# Sheet5_old.net
KiCad netlist of a schematic drawn in Altium Designer
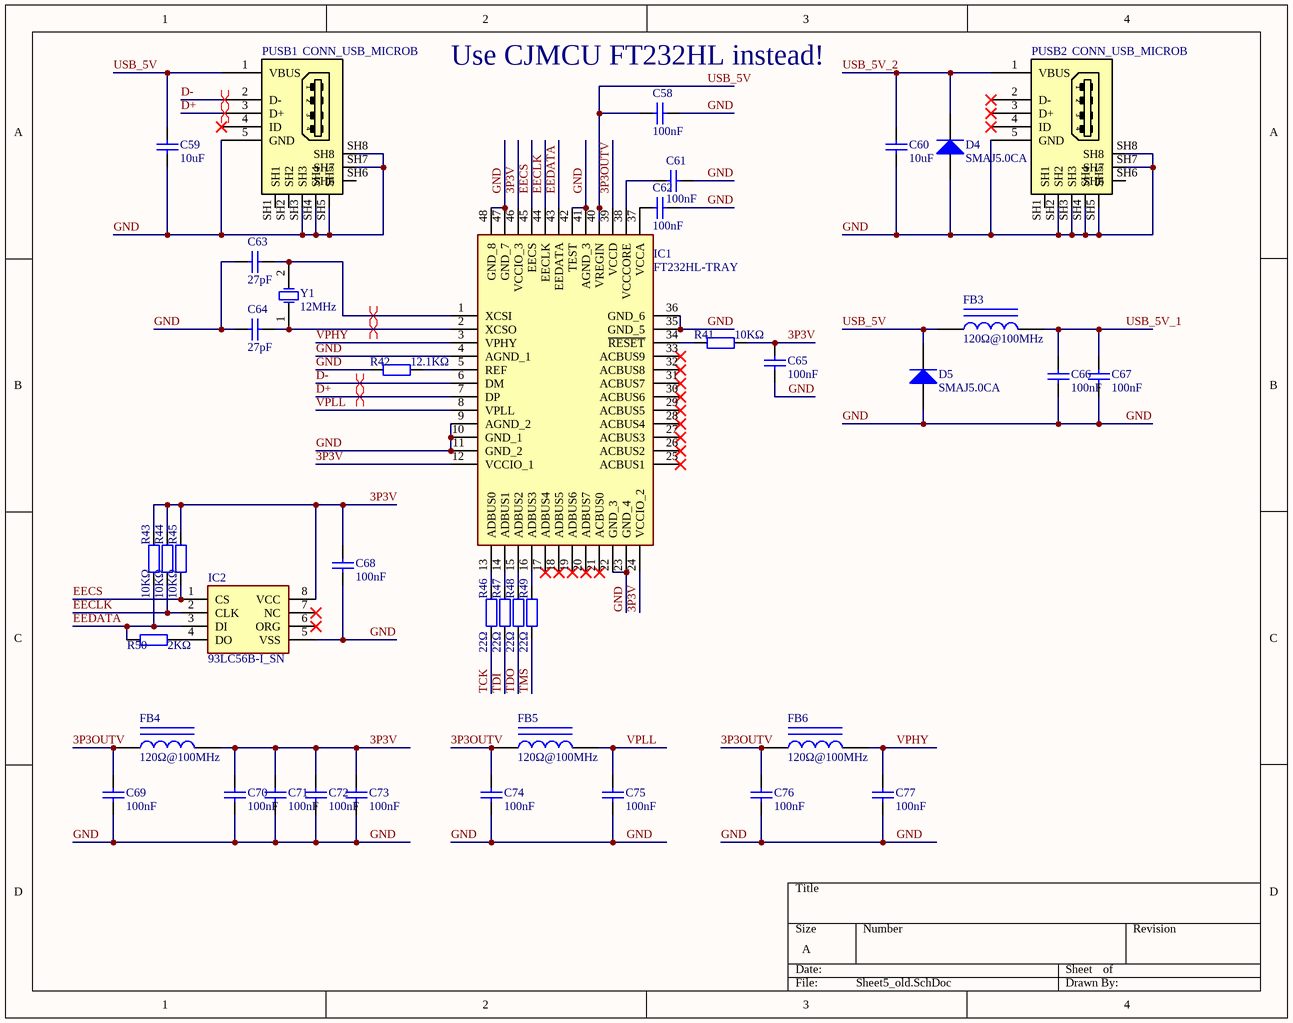
[diagram p0: Sheet5_old.SchDoc]

(export (version "E")
  (design (tool "Eeschema 10.0.6"))
  (components
    (comp (ref "C58")
      (value "100nF")
      (footprint "1206_C")
      (description "贴片电容")
      (libsource (lib "Cap") (part "1206 100nF (104) 10% 50V"))
    )
    (comp (ref "C59")
      (value "10uF")
      (footprint "1206_C")
      (description "贴片电容")
      (libsource (lib "Cap") (part "1206 10uF (106) 10% 50V"))
    )
    (comp (ref "C60")
      (value "10uF")
      (footprint "1206_C")
      (description "贴片电容")
      (libsource (lib "Cap") (part "1206 10uF (106) 10% 50V"))
    )
    (comp (ref "C61")
      (value "100nF")
      (footprint "1206_C")
      (description "贴片电容")
      (libsource (lib "Cap") (part "1206 100nF (104) 10% 50V"))
    )
    (comp (ref "C62")
      (value "100nF")
      (footprint "1206_C")
      (description "贴片电容")
      (libsource (lib "Cap") (part "1206 100nF (104) 10% 50V"))
    )
    (comp (ref "C63")
      (value "27pF")
      (footprint "0805_C")
      (description "贴片电容")
      (libsource (lib "Cap") (part "0805 27pF (270) 5% 50V"))
    )
    (comp (ref "C64")
      (value "27pF")
      (footprint "0805_C")
      (description "贴片电容")
      (libsource (lib "Cap") (part "0805 27pF (270) 5% 50V"))
    )
    (comp (ref "C65")
      (value "100nF")
      (footprint "1206_C")
      (description "贴片电容")
      (libsource (lib "Cap") (part "1206 100nF (104) 10% 50V"))
    )
    (comp (ref "C66")
      (value "100nF")
      (footprint "1206_C")
      (description "贴片电容")
      (libsource (lib "Cap") (part "1206 100nF (104) 10% 50V"))
    )
    (comp (ref "C67")
      (value "100nF")
      (footprint "1206_C")
      (description "贴片电容")
      (libsource (lib "Cap") (part "1206 100nF (104) 10% 50V"))
    )
    (comp (ref "C68")
      (value "100nF")
      (footprint "1206_C")
      (description "贴片电容")
      (libsource (lib "Cap") (part "1206 100nF (104) 10% 50V"))
    )
    (comp (ref "C69")
      (value "100nF")
      (footprint "1206_C")
      (description "贴片电容")
      (libsource (lib "Cap") (part "1206 100nF (104) 10% 50V"))
    )
    (comp (ref "C70")
      (value "100nF")
      (footprint "1206_C")
      (description "贴片电容")
      (libsource (lib "Cap") (part "1206 100nF (104) 10% 50V"))
    )
    (comp (ref "C71")
      (value "100nF")
      (footprint "1206_C")
      (description "贴片电容")
      (libsource (lib "Cap") (part "1206 100nF (104) 10% 50V"))
    )
    (comp (ref "C72")
      (value "100nF")
      (footprint "1206_C")
      (description "贴片电容")
      (libsource (lib "Cap") (part "1206 100nF (104) 10% 50V"))
    )
    (comp (ref "C73")
      (value "100nF")
      (footprint "1206_C")
      (description "贴片电容")
      (libsource (lib "Cap") (part "1206 100nF (104) 10% 50V"))
    )
    (comp (ref "C74")
      (value "100nF")
      (footprint "1206_C")
      (description "贴片电容")
      (libsource (lib "Cap") (part "1206 100nF (104) 10% 50V"))
    )
    (comp (ref "C75")
      (value "100nF")
      (footprint "1206_C")
      (description "贴片电容")
      (libsource (lib "Cap") (part "1206 100nF (104) 10% 50V"))
    )
    (comp (ref "C76")
      (value "100nF")
      (footprint "1206_C")
      (description "贴片电容")
      (libsource (lib "Cap") (part "1206 100nF (104) 10% 50V"))
    )
    (comp (ref "C77")
      (value "100nF")
      (footprint "1206_C")
      (description "贴片电容")
      (libsource (lib "Cap") (part "1206 100nF (104) 10% 50V"))
    )
    (comp (ref "D4")
      (value "SMAJ5.0CA")
      (footprint "SMA(DO-214AC)_S1")
      (description "二极管 TVS")
      (libsource (lib "Diode") (part "SMA(DO-214AC) SS210"))
    )
    (comp (ref "D5")
      (value "SMAJ5.0CA")
      (footprint "SMA(DO-214AC)_S1")
      (description "二极管 TVS")
      (libsource (lib "Diode") (part "SMA(DO-214AC) SS210"))
    )
    (comp (ref "FB3")
      (value "120Ω@100MHz")
      (footprint "0805_L")
      (description "贴片磁珠")
      (libsource (lib "IUD") (part "0805 100Ω 25% 100MHz"))
    )
    (comp (ref "FB4")
      (value "120Ω@100MHz")
      (footprint "0805_L")
      (description "贴片磁珠")
      (libsource (lib "IUD") (part "0805 100Ω 25% 100MHz"))
    )
    (comp (ref "FB5")
      (value "120Ω@100MHz")
      (footprint "0805_L")
      (description "贴片磁珠")
      (libsource (lib "IUD") (part "0805 100Ω 25% 100MHz"))
    )
    (comp (ref "FB6")
      (value "120Ω@100MHz")
      (footprint "0805_L")
      (description "贴片磁珠")
      (libsource (lib "IUD") (part "0805 100Ω 25% 100MHz"))
    )
    (comp (ref "IC1")
      (value "FT232HL-TRAY")
      (footprint "SamacSys:QFP50P900X900X160-48N")
      (description "Integrated Circuit")
      (fields (field (name "MOUSER PART NUMBER") "895-FT232HL-TRAY"))
      (libsource (lib "*") (part "FT232HL-TRAY"))
    )
    (comp (ref "IC2")
      (value "93LC56B-I_SN")
      (footprint "SamacSys:SOIC127P600X175-8N")
      (description "Integrated Circuit")
      (fields
        (field (name "MANUFACTURER_PART_NUMBER") "93LC56B-I/SN")
        (field (name "MOUSER PART NUMBER") "579-93LC56BISN")
      )
      (libsource (lib "*") (part "93LC56B-I_SN"))
    )
    (comp (ref "PUSB1")
      (value "CONN_USB_MICROB")
      (footprint "USB_MICRO_B_BM_SHT1")
      (description "CONN, USB, MICRO B, R/A, SMD, BOTTOM MOUNT, SHT")
      (fields (field (name "MANF_P#") "47590-0001") (field (name "MANF") "MOLEX"))
      (libsource (lib "Connector USB") (part "CONN_USB_MICRO_B_BM_SHT1"))
    )
    (comp (ref "PUSB2")
      (value "CONN_USB_MICROB")
      (footprint "USB_MICRO_B_BM_SHT1")
      (description "CONN, USB, MICRO B, R/A, SMD, BOTTOM MOUNT, SHT")
      (fields (field (name "MANF_P#") "47590-0001") (field (name "MANF") "MOLEX"))
      (libsource (lib "Connector USB") (part "CONN_USB_MICRO_B_BM_SHT1"))
    )
    (comp (ref "R41")
      (value "10KΩ")
      (footprint "1206_R")
      (description "贴片电阻")
      (libsource (lib "RES") (part "1206 10KΩ (1002) 1%"))
    )
    (comp (ref "R42")
      (value "12.1KΩ")
      (footprint "0805_R")
      (description "贴片电阻 12.1k")
      (libsource (lib "RES") (part "0805 12KΩ (1202) 1%"))
    )
    (comp (ref "R43")
      (value "10KΩ")
      (footprint "1206_R")
      (description "贴片电阻")
      (libsource (lib "") (part "1206 10KΩ (1002) 1%_1"))
    )
    (comp (ref "R44")
      (value "10KΩ")
      (footprint "1206_R")
      (description "贴片电阻")
      (libsource (lib "") (part "1206 10KΩ (1002) 1%_1"))
    )
    (comp (ref "R45")
      (value "10KΩ")
      (footprint "1206_R")
      (description "贴片电阻")
      (libsource (lib "") (part "1206 10KΩ (1002) 1%_1"))
    )
    (comp (ref "R46")
      (value "22Ω")
      (footprint "1206_R")
      (description "贴片电阻")
      (libsource (lib "RES") (part "1206 22Ω (22R0) 1%"))
    )
    (comp (ref "R47")
      (value "22Ω")
      (footprint "1206_R")
      (description "贴片电阻")
      (libsource (lib "RES") (part "1206 22Ω (22R0) 1%"))
    )
    (comp (ref "R48")
      (value "22Ω")
      (footprint "1206_R")
      (description "贴片电阻")
      (libsource (lib "RES") (part "1206 22Ω (22R0) 1%"))
    )
    (comp (ref "R49")
      (value "22Ω")
      (footprint "1206_R")
      (description "贴片电阻")
      (libsource (lib "RES") (part "1206 22Ω (22R0) 1%"))
    )
    (comp (ref "R50")
      (value "2KΩ")
      (footprint "1206_R")
      (description "贴片电阻")
      (libsource (lib "RES") (part "1206 2KΩ (2001) 1%"))
    )
    (comp (ref "Y1")
      (value "12MHz")
      (footprint "SMD-5032_2P")
      (description "贴片晶振 12MHz")
      (libsource (lib "CrystalOscillator") (part "SMD-5032_2P 11.0592MHZ 20PF 20PPM"))
    )
  )
  (nets
    (net (code "1") (name "/3P3OUTV") (class "Default")
      (node (ref "C69") (pin "2") (pinfunction "2_2") (pintype "passive"))
      (node (ref "C74") (pin "2") (pinfunction "2_2") (pintype "passive"))
      (node (ref "C76") (pin "2") (pinfunction "2_2") (pintype "passive"))
      (node (ref "FB4") (pin "1") (pinfunction "1_1") (pintype "passive"))
      (node (ref "FB5") (pin "1") (pinfunction "1_1") (pintype "passive"))
      (node (ref "FB6") (pin "1") (pinfunction "1_1") (pintype "passive"))
      (node (ref "IC1") (pin "39") (pinfunction "VCCD_39") (pintype "passive"))
    )
    (net (code "2") (name "/3P3V") (class "Default")
      (node (ref "C65") (pin "2") (pinfunction "2_2") (pintype "passive"))
      (node (ref "C68") (pin "2") (pinfunction "2_2") (pintype "passive"))
      (node (ref "C70") (pin "2") (pinfunction "2_2") (pintype "passive"))
      (node (ref "C71") (pin "2") (pinfunction "2_2") (pintype "passive"))
      (node (ref "C72") (pin "2") (pinfunction "2_2") (pintype "passive"))
      (node (ref "C73") (pin "2") (pinfunction "2_2") (pintype "passive"))
      (node (ref "FB4") (pin "2") (pinfunction "2_2") (pintype "passive"))
      (node (ref "IC1") (pin "12") (pinfunction "VCCIO_1_12") (pintype "passive"))
      (node (ref "IC1") (pin "24") (pinfunction "VCCIO_2_24") (pintype "passive"))
      (node (ref "IC1") (pin "46") (pinfunction "VCCIO_3_46") (pintype "passive"))
      (node (ref "IC2") (pin "8") (pinfunction "VCC_8") (pintype "passive"))
      (node (ref "R41") (pin "2") (pinfunction "2_2") (pintype "passive"))
      (node (ref "R43") (pin "2") (pinfunction "2_2") (pintype "passive"))
      (node (ref "R44") (pin "2") (pinfunction "2_2") (pintype "passive"))
      (node (ref "R45") (pin "2") (pinfunction "2_2") (pintype "passive"))
    )
    (net (code "3") (name "/D+") (class "Default")
      (node (ref "IC1") (pin "7") (pinfunction "DP_7") (pintype "passive"))
      (node (ref "PUSB1") (pin "3") (pinfunction "D+_3") (pintype "passive"))
    )
    (net (code "4") (name "/D-") (class "Default")
      (node (ref "IC1") (pin "6") (pinfunction "DM_6") (pintype "passive"))
      (node (ref "PUSB1") (pin "2") (pinfunction "D-_2") (pintype "passive"))
    )
    (net (code "5") (name "/EECLK") (class "Default")
      (node (ref "IC1") (pin "44") (pinfunction "EECLK_44") (pintype "passive"))
      (node (ref "IC2") (pin "2") (pinfunction "CLK_2") (pintype "passive"))
      (node (ref "R44") (pin "1") (pinfunction "1_1") (pintype "passive"))
    )
    (net (code "6") (name "/EECS") (class "Default")
      (node (ref "IC1") (pin "45") (pinfunction "EECS_45") (pintype "passive"))
      (node (ref "IC2") (pin "1") (pinfunction "CS_1") (pintype "passive"))
      (node (ref "R45") (pin "1") (pinfunction "1_1") (pintype "passive"))
    )
    (net (code "7") (name "/EEDATA") (class "Default")
      (node (ref "IC1") (pin "43") (pinfunction "EEDATA_43") (pintype "passive"))
      (node (ref "IC2") (pin "3") (pinfunction "DI_3") (pintype "passive"))
      (node (ref "R43") (pin "1") (pinfunction "1_1") (pintype "passive"))
      (node (ref "R50") (pin "1") (pinfunction "1_1") (pintype "passive"))
    )
    (net (code "8") (name "/GND") (class "Default")
      (node (ref "C58") (pin "2") (pinfunction "2_2") (pintype "passive"))
      (node (ref "C59") (pin "1") (pinfunction "1_1") (pintype "passive"))
      (node (ref "C60") (pin "1") (pinfunction "1_1") (pintype "passive"))
      (node (ref "C61") (pin "2") (pinfunction "2_2") (pintype "passive"))
      (node (ref "C62") (pin "2") (pinfunction "2_2") (pintype "passive"))
      (node (ref "C63") (pin "1") (pinfunction "1_1") (pintype "passive"))
      (node (ref "C64") (pin "1") (pinfunction "1_1") (pintype "passive"))
      (node (ref "C65") (pin "1") (pinfunction "1_1") (pintype "passive"))
      (node (ref "C66") (pin "1") (pinfunction "1_1") (pintype "passive"))
      (node (ref "C67") (pin "1") (pinfunction "1_1") (pintype "passive"))
      (node (ref "C68") (pin "1") (pinfunction "1_1") (pintype "passive"))
      (node (ref "C69") (pin "1") (pinfunction "1_1") (pintype "passive"))
      (node (ref "C70") (pin "1") (pinfunction "1_1") (pintype "passive"))
      (node (ref "C71") (pin "1") (pinfunction "1_1") (pintype "passive"))
      (node (ref "C72") (pin "1") (pinfunction "1_1") (pintype "passive"))
      (node (ref "C73") (pin "1") (pinfunction "1_1") (pintype "passive"))
      (node (ref "C74") (pin "1") (pinfunction "1_1") (pintype "passive"))
      (node (ref "C75") (pin "1") (pinfunction "1_1") (pintype "passive"))
      (node (ref "C76") (pin "1") (pinfunction "1_1") (pintype "passive"))
      (node (ref "C77") (pin "1") (pinfunction "1_1") (pintype "passive"))
      (node (ref "D4") (pin "1") (pinfunction "A_1") (pintype "passive"))
      (node (ref "D5") (pin "1") (pinfunction "A_1") (pintype "passive"))
      (node (ref "IC1") (pin "10") (pinfunction "GND_1_10") (pintype "passive"))
      (node (ref "IC1") (pin "11") (pinfunction "GND_2_11") (pintype "passive"))
      (node (ref "IC1") (pin "22") (pinfunction "GND_3_22") (pintype "passive"))
      (node (ref "IC1") (pin "23") (pinfunction "GND_4_23") (pintype "passive"))
      (node (ref "IC1") (pin "35") (pinfunction "GND_5_35") (pintype "passive"))
      (node (ref "IC1") (pin "36") (pinfunction "GND_6_36") (pintype "passive"))
      (node (ref "IC1") (pin "4") (pinfunction "AGND_1_4") (pintype "passive"))
      (node (ref "IC1") (pin "41") (pinfunction "AGND_3_41") (pintype "passive"))
      (node (ref "IC1") (pin "42") (pinfunction "TEST_42") (pintype "passive"))
      (node (ref "IC1") (pin "47") (pinfunction "GND_7_47") (pintype "passive"))
      (node (ref "IC1") (pin "48") (pinfunction "GND_8_48") (pintype "passive"))
      (node (ref "IC1") (pin "9") (pinfunction "AGND_2_9") (pintype "passive"))
      (node (ref "IC2") (pin "5") (pinfunction "VSS_5") (pintype "passive"))
      (node (ref "PUSB1") (pin "5") (pinfunction "GND_5") (pintype "power_in"))
      (node (ref "PUSB1") (pin "SH3") (pinfunction "SH3_SH3") (pintype "passive"))
      (node (ref "PUSB1") (pin "SH4") (pinfunction "SH4_SH4") (pintype "passive"))
      (node (ref "PUSB1") (pin "SH5") (pinfunction "SH5_SH5") (pintype "passive"))
      (node (ref "PUSB1") (pin "SH7") (pinfunction "SH7_SH7") (pintype "passive"))
      (node (ref "PUSB1") (pin "SH8") (pinfunction "SH8_SH8") (pintype "passive"))
      (node (ref "PUSB2") (pin "5") (pinfunction "GND_5") (pintype "power_in"))
      (node (ref "PUSB2") (pin "SH2") (pinfunction "SH2_SH2") (pintype "passive"))
      (node (ref "PUSB2") (pin "SH3") (pinfunction "SH3_SH3") (pintype "passive"))
      (node (ref "PUSB2") (pin "SH4") (pinfunction "SH4_SH4") (pintype "passive"))
      (node (ref "PUSB2") (pin "SH5") (pinfunction "SH5_SH5") (pintype "passive"))
      (node (ref "PUSB2") (pin "SH7") (pinfunction "SH7_SH7") (pintype "passive"))
      (node (ref "PUSB2") (pin "SH8") (pinfunction "SH8_SH8") (pintype "passive"))
      (node (ref "R42") (pin "1") (pinfunction "1_1") (pintype "passive"))
    )
    (net (code "9") (name "/TCK") (class "Default")
      (node (ref "R46") (pin "1") (pinfunction "1_1") (pintype "passive"))
    )
    (net (code "10") (name "/TDI") (class "Default")
      (node (ref "R47") (pin "1") (pinfunction "1_1") (pintype "passive"))
    )
    (net (code "11") (name "/TDO") (class "Default")
      (node (ref "R48") (pin "1") (pinfunction "1_1") (pintype "passive"))
    )
    (net (code "12") (name "/TMS") (class "Default")
      (node (ref "R49") (pin "1") (pinfunction "1_1") (pintype "passive"))
    )
    (net (code "13") (name "/USB_5V") (class "Default")
      (node (ref "C58") (pin "1") (pinfunction "1_1") (pintype "passive"))
      (node (ref "C59") (pin "2") (pinfunction "2_2") (pintype "passive"))
      (node (ref "D5") (pin "2") (pinfunction "K_2") (pintype "passive"))
      (node (ref "FB3") (pin "1") (pinfunction "1_1") (pintype "passive"))
      (node (ref "IC1") (pin "40") (pinfunction "VREGIN_40") (pintype "passive"))
      (node (ref "PUSB1") (pin "1") (pinfunction "VBUS_1") (pintype "power_in"))
    )
    (net (code "14") (name "/USB_5V_1") (class "Default")
      (node (ref "C66") (pin "2") (pinfunction "2_2") (pintype "passive"))
      (node (ref "C67") (pin "2") (pinfunction "2_2") (pintype "passive"))
      (node (ref "FB3") (pin "2") (pinfunction "2_2") (pintype "passive"))
    )
    (net (code "15") (name "/USB_5V_2") (class "Default")
      (node (ref "C60") (pin "2") (pinfunction "2_2") (pintype "passive"))
      (node (ref "D4") (pin "2") (pinfunction "K_2") (pintype "passive"))
      (node (ref "PUSB2") (pin "1") (pinfunction "VBUS_1") (pintype "power_in"))
    )
    (net (code "16") (name "/VPHY") (class "Default")
      (node (ref "C77") (pin "2") (pinfunction "2_2") (pintype "passive"))
      (node (ref "FB6") (pin "2") (pinfunction "2_2") (pintype "passive"))
      (node (ref "IC1") (pin "3") (pinfunction "VPHY_3") (pintype "passive"))
    )
    (net (code "17") (name "/VPLL") (class "Default")
      (node (ref "C75") (pin "2") (pinfunction "2_2") (pintype "passive"))
      (node (ref "FB5") (pin "2") (pinfunction "2_2") (pintype "passive"))
      (node (ref "IC1") (pin "8") (pinfunction "VPLL_8") (pintype "passive"))
    )
    (net (code "18") (name "Net-(IC1-ADBUS0)") (class "Default")
      (node (ref "IC1") (pin "13") (pinfunction "ADBUS0_13") (pintype "passive"))
      (node (ref "R46") (pin "2") (pinfunction "2_2") (pintype "passive"))
    )
    (net (code "19") (name "Net-(IC1-ADBUS1)") (class "Default")
      (node (ref "IC1") (pin "14") (pinfunction "ADBUS1_14") (pintype "passive"))
      (node (ref "R47") (pin "2") (pinfunction "2_2") (pintype "passive"))
    )
    (net (code "20") (name "Net-(IC1-ADBUS2)") (class "Default")
      (node (ref "IC1") (pin "15") (pinfunction "ADBUS2_15") (pintype "passive"))
      (node (ref "R48") (pin "2") (pinfunction "2_2") (pintype "passive"))
    )
    (net (code "21") (name "Net-(IC1-ADBUS3)") (class "Default")
      (node (ref "IC1") (pin "16") (pinfunction "ADBUS3_16") (pintype "passive"))
      (node (ref "R49") (pin "2") (pinfunction "2_2") (pintype "passive"))
    )
    (net (code "22") (name "Net-(IC1-REF)") (class "Default")
      (node (ref "IC1") (pin "5") (pinfunction "REF_5") (pintype "passive"))
      (node (ref "R42") (pin "2") (pinfunction "2_2") (pintype "passive"))
    )
    (net (code "23") (name "Net-(IC1-VCCA)") (class "Default")
      (node (ref "C62") (pin "1") (pinfunction "1_1") (pintype "passive"))
      (node (ref "IC1") (pin "37") (pinfunction "VCCA_37") (pintype "passive"))
    )
    (net (code "24") (name "Net-(IC1-VCCCORE)") (class "Default")
      (node (ref "C61") (pin "1") (pinfunction "1_1") (pintype "passive"))
      (node (ref "IC1") (pin "38") (pinfunction "VCCCORE_38") (pintype "passive"))
    )
    (net (code "25") (name "Net-(IC1-XCSI)") (class "Default")
      (node (ref "C63") (pin "2") (pinfunction "2_2") (pintype "passive"))
      (node (ref "IC1") (pin "1") (pinfunction "XCSI_1") (pintype "passive"))
      (node (ref "Y1") (pin "2") (pinfunction "OSC2_2") (pintype "passive"))
    )
    (net (code "26") (name "Net-(IC1-XCSO)") (class "Default")
      (node (ref "C64") (pin "2") (pinfunction "2_2") (pintype "passive"))
      (node (ref "IC1") (pin "2") (pinfunction "XCSO_2") (pintype "passive"))
      (node (ref "Y1") (pin "1") (pinfunction "OSC1_1") (pintype "passive"))
    )
    (net (code "27") (name "Net-(IC1-~{RESET})") (class "Default")
      (node (ref "IC1") (pin "34") (pinfunction "~{RESET}_34") (pintype "passive"))
      (node (ref "R41") (pin "1") (pinfunction "1_1") (pintype "passive"))
    )
    (net (code "28") (name "Net-(IC2-DO)") (class "Default")
      (node (ref "IC2") (pin "4") (pinfunction "DO_4") (pintype "passive"))
      (node (ref "R50") (pin "2") (pinfunction "2_2") (pintype "passive"))
    )
    (net (code "29") (name "unconnected-(IC1-ACBUS0-Pad21)") (class "Default")
      (node (ref "IC1") (pin "21") (pinfunction "ACBUS0_21") (pintype "passive+no_connect"))
    )
    (net (code "30") (name "unconnected-(IC1-ACBUS1-Pad25)") (class "Default")
      (node (ref "IC1") (pin "25") (pinfunction "ACBUS1_25") (pintype "passive+no_connect"))
    )
    (net (code "31") (name "unconnected-(IC1-ACBUS2-Pad26)") (class "Default")
      (node (ref "IC1") (pin "26") (pinfunction "ACBUS2_26") (pintype "passive+no_connect"))
    )
    (net (code "32") (name "unconnected-(IC1-ACBUS3-Pad27)") (class "Default")
      (node (ref "IC1") (pin "27") (pinfunction "ACBUS3_27") (pintype "passive+no_connect"))
    )
    (net (code "33") (name "unconnected-(IC1-ACBUS4-Pad28)") (class "Default")
      (node (ref "IC1") (pin "28") (pinfunction "ACBUS4_28") (pintype "passive+no_connect"))
    )
    (net (code "34") (name "unconnected-(IC1-ACBUS5-Pad29)") (class "Default")
      (node (ref "IC1") (pin "29") (pinfunction "ACBUS5_29") (pintype "passive+no_connect"))
    )
    (net (code "35") (name "unconnected-(IC1-ACBUS6-Pad30)") (class "Default")
      (node (ref "IC1") (pin "30") (pinfunction "ACBUS6_30") (pintype "passive+no_connect"))
    )
    (net (code "36") (name "unconnected-(IC1-ACBUS7-Pad31)") (class "Default")
      (node (ref "IC1") (pin "31") (pinfunction "ACBUS7_31") (pintype "passive+no_connect"))
    )
    (net (code "37") (name "unconnected-(IC1-ACBUS8-Pad32)") (class "Default")
      (node (ref "IC1") (pin "32") (pinfunction "ACBUS8_32") (pintype "passive+no_connect"))
    )
    (net (code "38") (name "unconnected-(IC1-ACBUS9-Pad33)") (class "Default")
      (node (ref "IC1") (pin "33") (pinfunction "ACBUS9_33") (pintype "passive+no_connect"))
    )
    (net (code "39") (name "unconnected-(IC1-ADBUS4-Pad17)") (class "Default")
      (node (ref "IC1") (pin "17") (pinfunction "ADBUS4_17") (pintype "passive+no_connect"))
    )
    (net (code "40") (name "unconnected-(IC1-ADBUS5-Pad18)") (class "Default")
      (node (ref "IC1") (pin "18") (pinfunction "ADBUS5_18") (pintype "passive+no_connect"))
    )
    (net (code "41") (name "unconnected-(IC1-ADBUS6-Pad19)") (class "Default")
      (node (ref "IC1") (pin "19") (pinfunction "ADBUS6_19") (pintype "passive+no_connect"))
    )
    (net (code "42") (name "unconnected-(IC1-ADBUS7-Pad20)") (class "Default")
      (node (ref "IC1") (pin "20") (pinfunction "ADBUS7_20") (pintype "passive+no_connect"))
    )
    (net (code "43") (name "unconnected-(IC2-NC-Pad7)") (class "Default")
      (node (ref "IC2") (pin "7") (pinfunction "NC_7") (pintype "passive+no_connect"))
    )
    (net (code "44") (name "unconnected-(IC2-ORG-Pad6)") (class "Default")
      (node (ref "IC2") (pin "6") (pinfunction "ORG_6") (pintype "passive+no_connect"))
    )
    (net (code "45") (name "unconnected-(PUSB1-ID-Pad4)") (class "Default")
      (node (ref "PUSB1") (pin "4") (pinfunction "ID_4") (pintype "power_in+no_connect"))
    )
    (net (code "46") (name "unconnected-(PUSB1-PadSH1)") (class "Default")
      (node (ref "PUSB1") (pin "SH1") (pinfunction "SH1_SH1") (pintype "passive"))
    )
    (net (code "47") (name "unconnected-(PUSB1-PadSH2)") (class "Default")
      (node (ref "PUSB1") (pin "SH2") (pinfunction "SH2_SH2") (pintype "passive"))
    )
    (net (code "48") (name "unconnected-(PUSB1-PadSH6)") (class "Default")
      (node (ref "PUSB1") (pin "SH6") (pinfunction "SH6_SH6") (pintype "passive"))
    )
    (net (code "49") (name "unconnected-(PUSB2-D+-Pad3)") (class "Default")
      (node (ref "PUSB2") (pin "3") (pinfunction "D+_3") (pintype "passive+no_connect"))
    )
    (net (code "50") (name "unconnected-(PUSB2-D--Pad2)") (class "Default")
      (node (ref "PUSB2") (pin "2") (pinfunction "D-_2") (pintype "passive+no_connect"))
    )
    (net (code "51") (name "unconnected-(PUSB2-ID-Pad4)") (class "Default")
      (node (ref "PUSB2") (pin "4") (pinfunction "ID_4") (pintype "power_in+no_connect"))
    )
    (net (code "52") (name "unconnected-(PUSB2-PadSH1)") (class "Default")
      (node (ref "PUSB2") (pin "SH1") (pinfunction "SH1_SH1") (pintype "passive"))
    )
    (net (code "53") (name "unconnected-(PUSB2-PadSH6)") (class "Default")
      (node (ref "PUSB2") (pin "SH6") (pinfunction "SH6_SH6") (pintype "passive"))
    )
  )
)
